# ExploraRoverRobot_MotorsControllerSystem.net
KiCad netlist of a schematic drawn in EAGLE
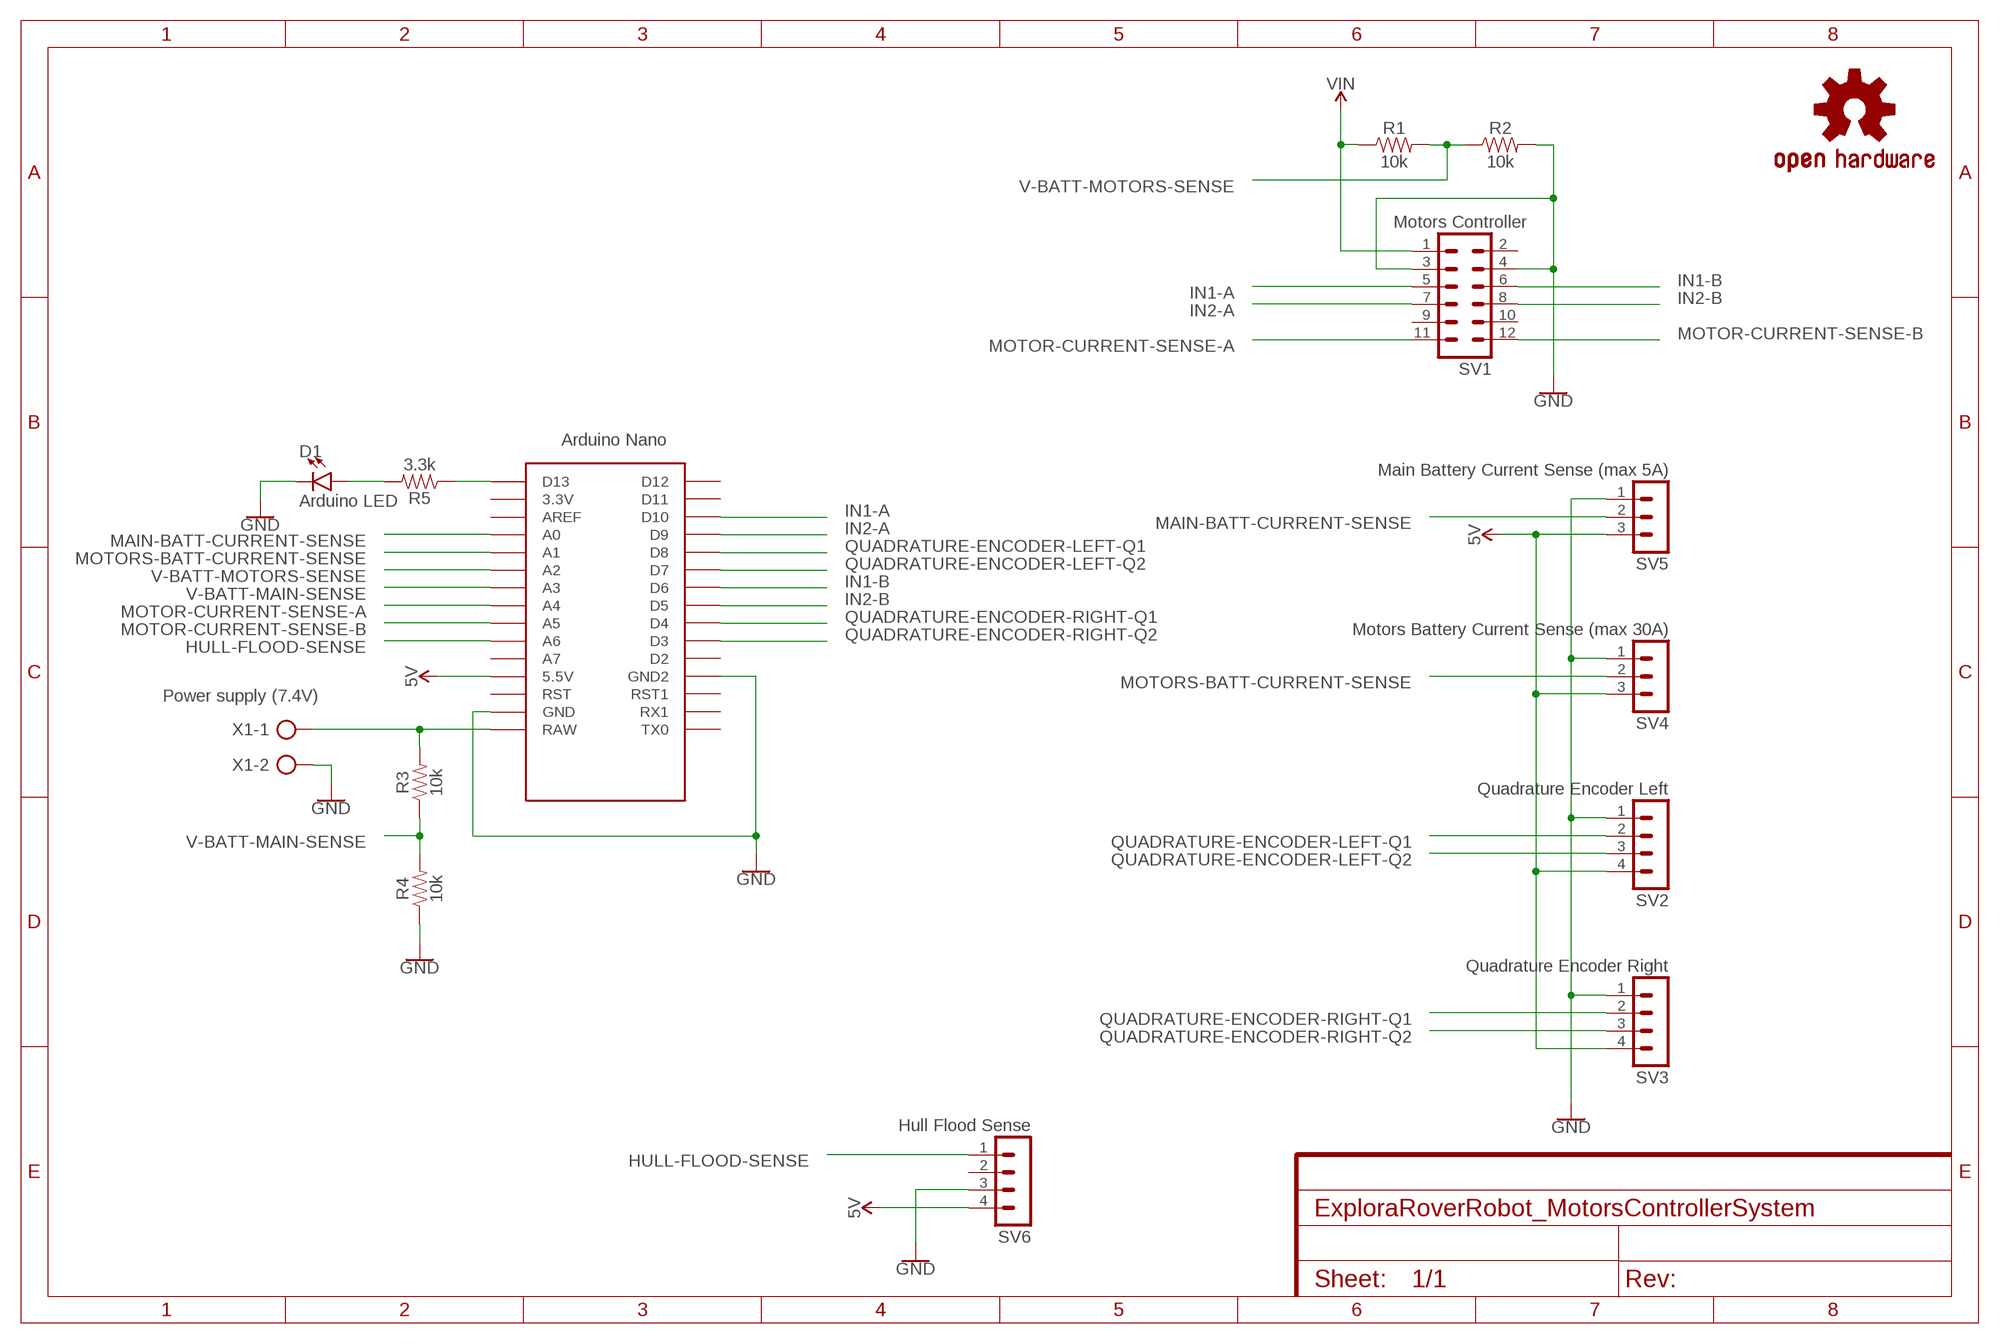
[diagram p0: schematic, sheet 1]

(export (version "E")
  (design (tool "Eeschema 10.0.6"))
  (components
    (comp (ref "D1")
      (value "Arduino LED")
      (footprint "eagle-import:LED_3MM")
      (libsource (lib "eagle-import") (part "LED3MM"))
    )
    (comp (ref "LOGO1")
      (value "OSHW-LOGOL")
      (footprint "eagle-import:OSHW-LOGO-L")
      (libsource (lib "eagle-import") (part "OSHW-LOGOL"))
    )
    (comp (ref "R1")
      (value "10k")
      (footprint "eagle-import:0603")
      (libsource (lib "eagle-import") (part "10KOHM-0603-1/10W-1%"))
    )
    (comp (ref "R2")
      (value "10k")
      (footprint "eagle-import:0603")
      (libsource (lib "eagle-import") (part "10KOHM-0603-1/10W-1%"))
    )
    (comp (ref "R3")
      (value "10k")
      (footprint "eagle-import:0603")
      (libsource (lib "eagle-import") (part "10KOHM-0603-1/10W-1%"))
    )
    (comp (ref "R4")
      (value "10k")
      (footprint "eagle-import:0603")
      (libsource (lib "eagle-import") (part "10KOHM-0603-1/10W-1%"))
    )
    (comp (ref "R5")
      (value "3.3k")
      (footprint "eagle-import:0603")
      (libsource (lib "eagle-import") (part "10KOHM-0603-1/10W-1%"))
    )
    (comp (ref "SV1")
      (value "Motors Controller")
      (footprint "eagle-import:MA06-2")
      (libsource (lib "eagle-import") (part "MA06-2"))
    )
    (comp (ref "SV2")
      (value "Quadrature Encoder Left")
      (footprint "eagle-import:MA04-1")
      (libsource (lib "eagle-import") (part "MA04-1"))
    )
    (comp (ref "SV3")
      (value "Quadrature Encoder Right")
      (footprint "eagle-import:MA04-1")
      (libsource (lib "eagle-import") (part "MA04-1"))
    )
    (comp (ref "SV4")
      (value "Motors Battery Current Sense (max 30A)")
      (footprint "eagle-import:MA03-1")
      (libsource (lib "eagle-import") (part "MA03-1"))
    )
    (comp (ref "SV5")
      (value "Main Battery Current Sense (max 5A)")
      (footprint "eagle-import:MA03-1")
      (libsource (lib "eagle-import") (part "MA03-1"))
    )
    (comp (ref "SV6")
      (value "Hull Flood Sense")
      (footprint "eagle-import:MA04-1")
      (libsource (lib "eagle-import") (part "MA04-1"))
    )
    (comp (ref "U$1")
      (value "NANO")
      (footprint "eagle-import:NANO")
      (libsource (lib "eagle-import") (part "NANO"))
    )
    (comp (ref "X1")
      (value "Power supply (7.4V)")
      (footprint "eagle-import:AK500_2")
      (libsource (lib "eagle-import") (part "AK500/2"))
    )
  )
  (nets
    (net (code "1") (name "/HULL-FLOOD-SENSE") (class "Default")
      (node (ref "SV6") (pin "1") (pinfunction "1_1") (pintype "passive"))
      (node (ref "U$1") (pin "A6") (pinfunction "A6_A6") (pintype "bidirectional"))
    )
    (net (code "2") (name "/IN1-A") (class "Default")
      (node (ref "SV1") (pin "5") (pinfunction "5_5") (pintype "passive"))
      (node (ref "U$1") (pin "D10") (pinfunction "D10_D10") (pintype "bidirectional"))
    )
    (net (code "3") (name "/IN1-B") (class "Default")
      (node (ref "SV1") (pin "6") (pinfunction "6_6") (pintype "passive"))
      (node (ref "U$1") (pin "D6") (pinfunction "D6_D6") (pintype "bidirectional"))
    )
    (net (code "4") (name "/IN2-A") (class "Default")
      (node (ref "SV1") (pin "7") (pinfunction "7_7") (pintype "passive"))
      (node (ref "U$1") (pin "D9") (pinfunction "D9_D9") (pintype "bidirectional"))
    )
    (net (code "5") (name "/IN2-B") (class "Default")
      (node (ref "SV1") (pin "8") (pinfunction "8_8") (pintype "passive"))
      (node (ref "U$1") (pin "D5") (pinfunction "D5_D5") (pintype "bidirectional"))
    )
    (net (code "6") (name "/MAIN-BATT-CURRENT-SENSE") (class "Default")
      (node (ref "SV5") (pin "2") (pinfunction "2_2") (pintype "passive"))
      (node (ref "U$1") (pin "A0") (pinfunction "A0_A0") (pintype "bidirectional"))
    )
    (net (code "7") (name "/MOTOR-CURRENT-SENSE-A") (class "Default")
      (node (ref "SV1") (pin "11") (pinfunction "11_11") (pintype "passive"))
      (node (ref "U$1") (pin "A4") (pinfunction "A4_A4") (pintype "bidirectional"))
    )
    (net (code "8") (name "/MOTOR-CURRENT-SENSE-B") (class "Default")
      (node (ref "SV1") (pin "12") (pinfunction "12_12") (pintype "passive"))
      (node (ref "U$1") (pin "A5") (pinfunction "A5_A5") (pintype "bidirectional"))
    )
    (net (code "9") (name "/MOTORS-BATT-CURRENT-SENSE") (class "Default")
      (node (ref "SV4") (pin "2") (pinfunction "2_2") (pintype "passive"))
      (node (ref "U$1") (pin "A1") (pinfunction "A1_A1") (pintype "bidirectional"))
    )
    (net (code "10") (name "/QUADRATURE-ENCODER-LEFT-Q1") (class "Default")
      (node (ref "SV2") (pin "2") (pinfunction "2_2") (pintype "passive"))
      (node (ref "U$1") (pin "D8") (pinfunction "D8_D8") (pintype "bidirectional"))
    )
    (net (code "11") (name "/QUADRATURE-ENCODER-LEFT-Q2") (class "Default")
      (node (ref "SV2") (pin "3") (pinfunction "3_3") (pintype "passive"))
      (node (ref "U$1") (pin "D7") (pinfunction "D7_D7") (pintype "bidirectional"))
    )
    (net (code "12") (name "/QUADRATURE-ENCODER-RIGHT-Q1") (class "Default")
      (node (ref "SV3") (pin "2") (pinfunction "2_2") (pintype "passive"))
      (node (ref "U$1") (pin "D4") (pinfunction "D4_D4") (pintype "bidirectional"))
    )
    (net (code "13") (name "/QUADRATURE-ENCODER-RIGHT-Q2") (class "Default")
      (node (ref "SV3") (pin "3") (pinfunction "3_3") (pintype "passive"))
      (node (ref "U$1") (pin "D3") (pinfunction "D3_D3") (pintype "bidirectional"))
    )
    (net (code "14") (name "/V-BATT-MAIN-SENSE") (class "Default")
      (node (ref "R3") (pin "1") (pinfunction "1_1") (pintype "passive"))
      (node (ref "R4") (pin "2") (pinfunction "2_2") (pintype "passive"))
      (node (ref "U$1") (pin "A3") (pinfunction "A3_A3") (pintype "bidirectional"))
    )
    (net (code "15") (name "/V-BATT-MOTORS-SENSE") (class "Default")
      (node (ref "R1") (pin "2") (pinfunction "2_2") (pintype "passive"))
      (node (ref "R2") (pin "1") (pinfunction "1_1") (pintype "passive"))
      (node (ref "U$1") (pin "A2") (pinfunction "A2_A2") (pintype "bidirectional"))
    )
    (net (code "16") (name "5V") (class "Default")
      (node (ref "SV2") (pin "4") (pinfunction "4_4") (pintype "passive"))
      (node (ref "SV3") (pin "4") (pinfunction "4_4") (pintype "passive"))
      (node (ref "SV4") (pin "3") (pinfunction "3_3") (pintype "passive"))
      (node (ref "SV5") (pin "3") (pinfunction "3_3") (pintype "passive"))
      (node (ref "SV6") (pin "4") (pinfunction "4_4") (pintype "passive"))
      (node (ref "U$1") (pin "5V") (pinfunction "5.5V_5V") (pintype "bidirectional"))
    )
    (net (code "17") (name "GND") (class "Default")
      (node (ref "D1") (pin "K") (pinfunction "C_K") (pintype "passive"))
      (node (ref "R2") (pin "2") (pinfunction "2_2") (pintype "passive"))
      (node (ref "R4") (pin "1") (pinfunction "1_1") (pintype "passive"))
      (node (ref "SV1") (pin "3") (pinfunction "3_3") (pintype "passive"))
      (node (ref "SV1") (pin "4") (pinfunction "4_4") (pintype "passive"))
      (node (ref "SV2") (pin "1") (pinfunction "1_1") (pintype "passive"))
      (node (ref "SV3") (pin "1") (pinfunction "1_1") (pintype "passive"))
      (node (ref "SV4") (pin "1") (pinfunction "1_1") (pintype "passive"))
      (node (ref "SV5") (pin "1") (pinfunction "1_1") (pintype "passive"))
      (node (ref "SV6") (pin "3") (pinfunction "3_3") (pintype "passive"))
      (node (ref "U$1") (pin "GND") (pinfunction "GND_GND") (pintype "bidirectional"))
      (node (ref "U$1") (pin "GND1") (pinfunction "GND2_GND1") (pintype "bidirectional"))
      (node (ref "X1") (pin "2") (pinfunction "KL_2") (pintype "passive"))
    )
    (net (code "18") (name "Net-(D1-PadA)") (class "Default")
      (node (ref "D1") (pin "A") (pinfunction "A_A") (pintype "passive"))
      (node (ref "R5") (pin "2") (pinfunction "2_2") (pintype "passive"))
    )
    (net (code "19") (name "Net-(R5-Pad1)") (class "Default")
      (node (ref "R5") (pin "1") (pinfunction "1_1") (pintype "passive"))
      (node (ref "U$1") (pin "D13") (pinfunction "D13_D13") (pintype "bidirectional"))
    )
    (net (code "20") (name "Net-(X1A-KL)") (class "Default")
      (node (ref "R3") (pin "2") (pinfunction "2_2") (pintype "passive"))
      (node (ref "U$1") (pin "RAW") (pinfunction "RAW_RAW") (pintype "bidirectional"))
      (node (ref "X1") (pin "1") (pinfunction "KL_1") (pintype "passive"))
    )
    (net (code "21") (name "VIN") (class "Default")
      (node (ref "R1") (pin "1") (pinfunction "1_1") (pintype "passive"))
      (node (ref "SV1") (pin "1") (pinfunction "1_1") (pintype "passive"))
    )
    (net (code "22") (name "unconnected-(SV1-Pad2)") (class "Default")
      (node (ref "SV1") (pin "2") (pinfunction "2_2") (pintype "passive"))
    )
    (net (code "23") (name "unconnected-(SV1-Pad9)") (class "Default")
      (node (ref "SV1") (pin "9") (pinfunction "9_9") (pintype "passive"))
    )
    (net (code "24") (name "unconnected-(SV1-Pad10)") (class "Default")
      (node (ref "SV1") (pin "10") (pinfunction "10_10") (pintype "passive"))
    )
    (net (code "25") (name "unconnected-(SV6-Pad2)") (class "Default")
      (node (ref "SV6") (pin "2") (pinfunction "2_2") (pintype "passive"))
    )
    (net (code "26") (name "unconnected-(U$1-Pad3.3V)") (class "Default")
      (node (ref "U$1") (pin "3.3V") (pinfunction "3.3V_3.3V") (pintype "bidirectional"))
    )
    (net (code "27") (name "unconnected-(U$1-PadA7)") (class "Default")
      (node (ref "U$1") (pin "A7") (pinfunction "A7_A7") (pintype "bidirectional"))
    )
    (net (code "28") (name "unconnected-(U$1-PadAREF)") (class "Default")
      (node (ref "U$1") (pin "AREF") (pinfunction "AREF_AREF") (pintype "bidirectional"))
    )
    (net (code "29") (name "unconnected-(U$1-PadD2)") (class "Default")
      (node (ref "U$1") (pin "D2") (pinfunction "D2_D2") (pintype "bidirectional"))
    )
    (net (code "30") (name "unconnected-(U$1-PadD11)") (class "Default")
      (node (ref "U$1") (pin "D11") (pinfunction "D11_D11") (pintype "bidirectional"))
    )
    (net (code "31") (name "unconnected-(U$1-PadD12)") (class "Default")
      (node (ref "U$1") (pin "D12") (pinfunction "D12_D12") (pintype "bidirectional"))
    )
    (net (code "32") (name "unconnected-(U$1-PadICSP1)") (class "Default")
      (node (ref "U$1") (pin "ICSP1") (pinfunction "ICSP1_ICSP1") (pintype "bidirectional"))
    )
    (net (code "33") (name "unconnected-(U$1-PadICSP2)") (class "Default")
      (node (ref "U$1") (pin "ICSP2") (pinfunction "ICSP2_ICSP2") (pintype "bidirectional"))
    )
    (net (code "34") (name "unconnected-(U$1-PadICSP3)") (class "Default")
      (node (ref "U$1") (pin "ICSP3") (pinfunction "ICSP3_ICSP3") (pintype "bidirectional"))
    )
    (net (code "35") (name "unconnected-(U$1-PadICSP4)") (class "Default")
      (node (ref "U$1") (pin "ICSP4") (pinfunction "ICSP4_ICSP4") (pintype "bidirectional"))
    )
    (net (code "36") (name "unconnected-(U$1-PadICSP5)") (class "Default")
      (node (ref "U$1") (pin "ICSP5") (pinfunction "ICSP5_ICSP5") (pintype "bidirectional"))
    )
    (net (code "37") (name "unconnected-(U$1-PadICSP6)") (class "Default")
      (node (ref "U$1") (pin "ICSP6") (pinfunction "ICSP6_ICSP6") (pintype "bidirectional"))
    )
    (net (code "38") (name "unconnected-(U$1-PadRST)") (class "Default")
      (node (ref "U$1") (pin "RST") (pinfunction "RST_RST") (pintype "bidirectional"))
    )
    (net (code "39") (name "unconnected-(U$1-PadRST1)") (class "Default")
      (node (ref "U$1") (pin "RST1") (pinfunction "RST1_RST1") (pintype "bidirectional"))
    )
    (net (code "40") (name "unconnected-(U$1-PadRX1)") (class "Default")
      (node (ref "U$1") (pin "RX1") (pinfunction "RX1_RX1") (pintype "bidirectional"))
    )
    (net (code "41") (name "unconnected-(U$1-PadTX0)") (class "Default")
      (node (ref "U$1") (pin "TX0") (pinfunction "TX0_TX0") (pintype "bidirectional"))
    )
  )
)
